# container.net
KiCad netlist of a schematic drawn in Altium Designer
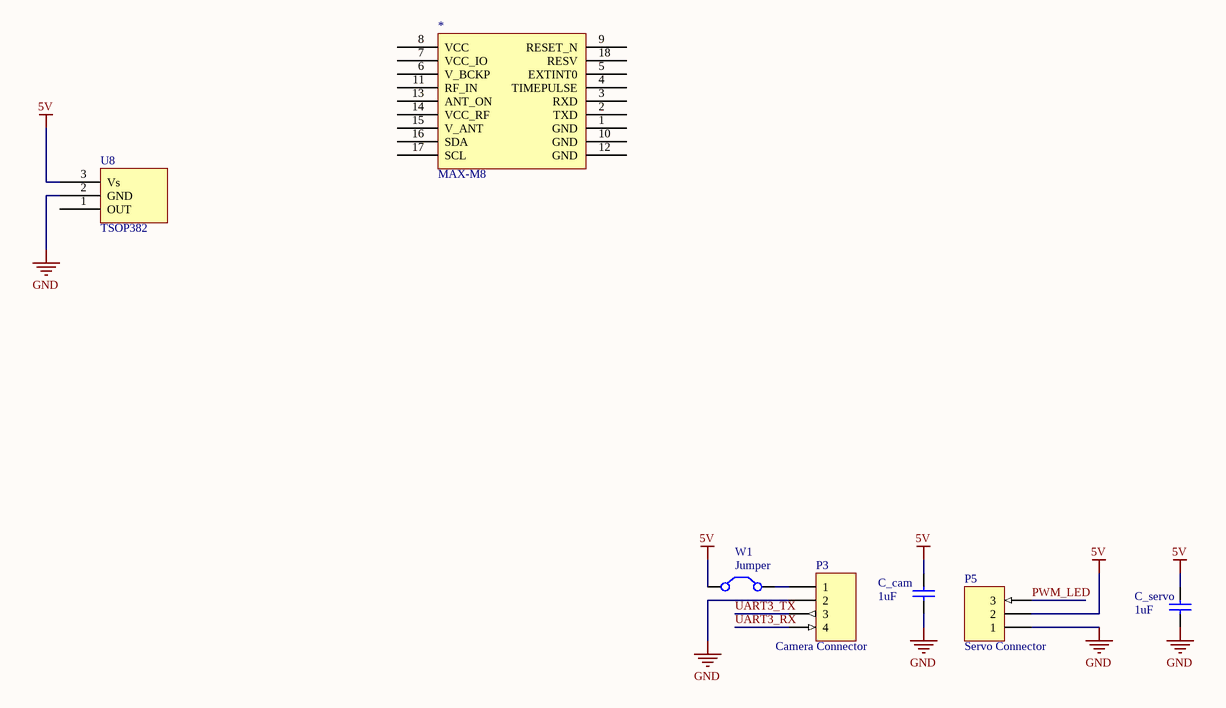
[diagram p0: container.SchDoc]

(export (version "E")
  (design (tool "Eeschema 10.0.6"))
  (components
    (comp (ref "*") (value "MAX-M8") (libsource (lib "Components") (part "MAX-M8")))
    (comp (ref "C_cam")
      (value "1uF")
      (footprint "1608[0603]")
      (description "Capacitor (Semiconductor SIM Model)")
      (fields (field (name "Comment") "Cap Semi") (field (name "PUBLISHER") "Altium Limited"))
      (libsource (lib "Miscellaneous Devices") (part "Cap Semi"))
    )
    (comp (ref "C_servo")
      (value "1uF")
      (footprint "1608[0603]")
      (description "Capacitor (Semiconductor SIM Model)")
      (fields (field (name "Comment") "Cap Semi") (field (name "PUBLISHER") "Altium Limited"))
      (libsource (lib "Miscellaneous Devices") (part "Cap Semi"))
    )
    (comp (ref "P3")
      (value "Camera Connector")
      (footprint "HDR1X4")
      (description "Header, 4-Pin")
      (fields (field (name "PUBLISHER") "Altium Limited"))
      (libsource (lib "Miscellaneous Connectors") (part "Header 4"))
    )
    (comp (ref "P5")
      (value "Servo Connector")
      (footprint "HDR1X3")
      (description "Header, 3-Pin")
      (fields (field (name "PUBLISHER") "Altium Limited"))
      (libsource (lib "Miscellaneous Connectors") (part "Header 3"))
    )
    (comp (ref "U8") (value "TSOP382") (libsource (lib "Components") (part "TSOP382")))
    (comp (ref "W1")
      (value "Jumper")
      (footprint "RAD-0.2")
      (description "Jumper Wire")
      (fields (field (name "PUBLISHER") "Altium Limited"))
      (libsource (lib "Miscellaneous Devices") (part "Jumper"))
    )
  )
  (nets
    (net (code "1") (name "/PWM_LED") (class "Default")
      (node (ref "P5") (pin "3") (pinfunction "3_3") (pintype "input"))
    )
    (net (code "2") (name "/UART3_RX") (class "Default")
      (node (ref "P3") (pin "4") (pinfunction "4_4") (pintype "input"))
    )
    (net (code "3") (name "/UART3_TX") (class "Default")
      (node (ref "P3") (pin "3") (pinfunction "3_3") (pintype "output"))
    )
    (net (code "4") (name "5V") (class "Default")
      (node (ref "C_cam") (pin "1") (pinfunction "1_1") (pintype "passive"))
      (node (ref "C_servo") (pin "1") (pinfunction "1_1") (pintype "passive"))
      (node (ref "P5") (pin "2") (pinfunction "2_2") (pintype "power_in"))
      (node (ref "U8") (pin "3") (pinfunction "Vs_3") (pintype "passive"))
      (node (ref "W1") (pin "1") (pinfunction "C1_1") (pintype "passive"))
    )
    (net (code "5") (name "GND") (class "Default")
      (node (ref "C_cam") (pin "2") (pinfunction "2_2") (pintype "passive"))
      (node (ref "C_servo") (pin "2") (pinfunction "2_2") (pintype "passive"))
      (node (ref "P3") (pin "2") (pinfunction "2_2") (pintype "power_in"))
      (node (ref "P5") (pin "1") (pinfunction "1_1") (pintype "power_in"))
      (node (ref "U8") (pin "2") (pinfunction "GND_2") (pintype "passive"))
    )
    (net (code "6") (name "Net-(W1-C2)") (class "Default")
      (node (ref "P3") (pin "1") (pinfunction "1_1") (pintype "power_in"))
      (node (ref "W1") (pin "2") (pinfunction "C2_2") (pintype "passive"))
    )
    (net (code "7") (name "unconnected-(*-ANT_ON-Pad13)") (class "Default")
      (node (ref "*") (pin "13") (pinfunction "ANT_ON_13") (pintype "passive"))
    )
    (net (code "8") (name "unconnected-(*-EXTINT0-Pad5)") (class "Default")
      (node (ref "*") (pin "5") (pinfunction "EXTINT0_5") (pintype "passive"))
    )
    (net (code "9") (name "unconnected-(*-GND-Pad1)") (class "Default")
      (node (ref "*") (pin "1") (pinfunction "GND_1") (pintype "passive"))
    )
    (net (code "10") (name "unconnected-(*-GND-Pad10)") (class "Default")
      (node (ref "*") (pin "10") (pinfunction "GND_10") (pintype "passive"))
    )
    (net (code "11") (name "unconnected-(*-GND-Pad12)") (class "Default")
      (node (ref "*") (pin "12") (pinfunction "GND_12") (pintype "passive"))
    )
    (net (code "12") (name "unconnected-(*-RESET_N-Pad9)") (class "Default")
      (node (ref "*") (pin "9") (pinfunction "RESET_N_9") (pintype "passive"))
    )
    (net (code "13") (name "unconnected-(*-RESV-Pad18)") (class "Default")
      (node (ref "*") (pin "18") (pinfunction "RESV_18") (pintype "passive"))
    )
    (net (code "14") (name "unconnected-(*-RF_IN-Pad11)") (class "Default")
      (node (ref "*") (pin "11") (pinfunction "RF_IN_11") (pintype "passive"))
    )
    (net (code "15") (name "unconnected-(*-RXD-Pad3)") (class "Default")
      (node (ref "*") (pin "3") (pinfunction "RXD_3") (pintype "passive"))
    )
    (net (code "16") (name "unconnected-(*-SCL-Pad17)") (class "Default")
      (node (ref "*") (pin "17") (pinfunction "SCL_17") (pintype "passive"))
    )
    (net (code "17") (name "unconnected-(*-SDA-Pad16)") (class "Default")
      (node (ref "*") (pin "16") (pinfunction "SDA_16") (pintype "passive"))
    )
    (net (code "18") (name "unconnected-(*-TIMEPULSE-Pad4)") (class "Default")
      (node (ref "*") (pin "4") (pinfunction "TIMEPULSE_4") (pintype "passive"))
    )
    (net (code "19") (name "unconnected-(*-TXD-Pad2)") (class "Default")
      (node (ref "*") (pin "2") (pinfunction "TXD_2") (pintype "passive"))
    )
    (net (code "20") (name "unconnected-(*-VCC-Pad8)") (class "Default")
      (node (ref "*") (pin "8") (pinfunction "VCC_8") (pintype "passive"))
    )
    (net (code "21") (name "unconnected-(*-VCC_IO-Pad7)") (class "Default")
      (node (ref "*") (pin "7") (pinfunction "VCC_IO_7") (pintype "passive"))
    )
    (net (code "22") (name "unconnected-(*-VCC_RF-Pad14)") (class "Default")
      (node (ref "*") (pin "14") (pinfunction "VCC_RF_14") (pintype "passive"))
    )
    (net (code "23") (name "unconnected-(*-V_ANT-Pad15)") (class "Default")
      (node (ref "*") (pin "15") (pinfunction "V_ANT_15") (pintype "passive"))
    )
    (net (code "24") (name "unconnected-(*-V_BCKP-Pad6)") (class "Default")
      (node (ref "*") (pin "6") (pinfunction "V_BCKP_6") (pintype "passive"))
    )
    (net (code "25") (name "unconnected-(U8-OUT-Pad1)") (class "Default")
      (node (ref "U8") (pin "1") (pinfunction "OUT_1") (pintype "passive"))
    )
  )
)
